# LumaFix64v1_2_sp.net
KiCad netlist of a schematic drawn in EAGLE
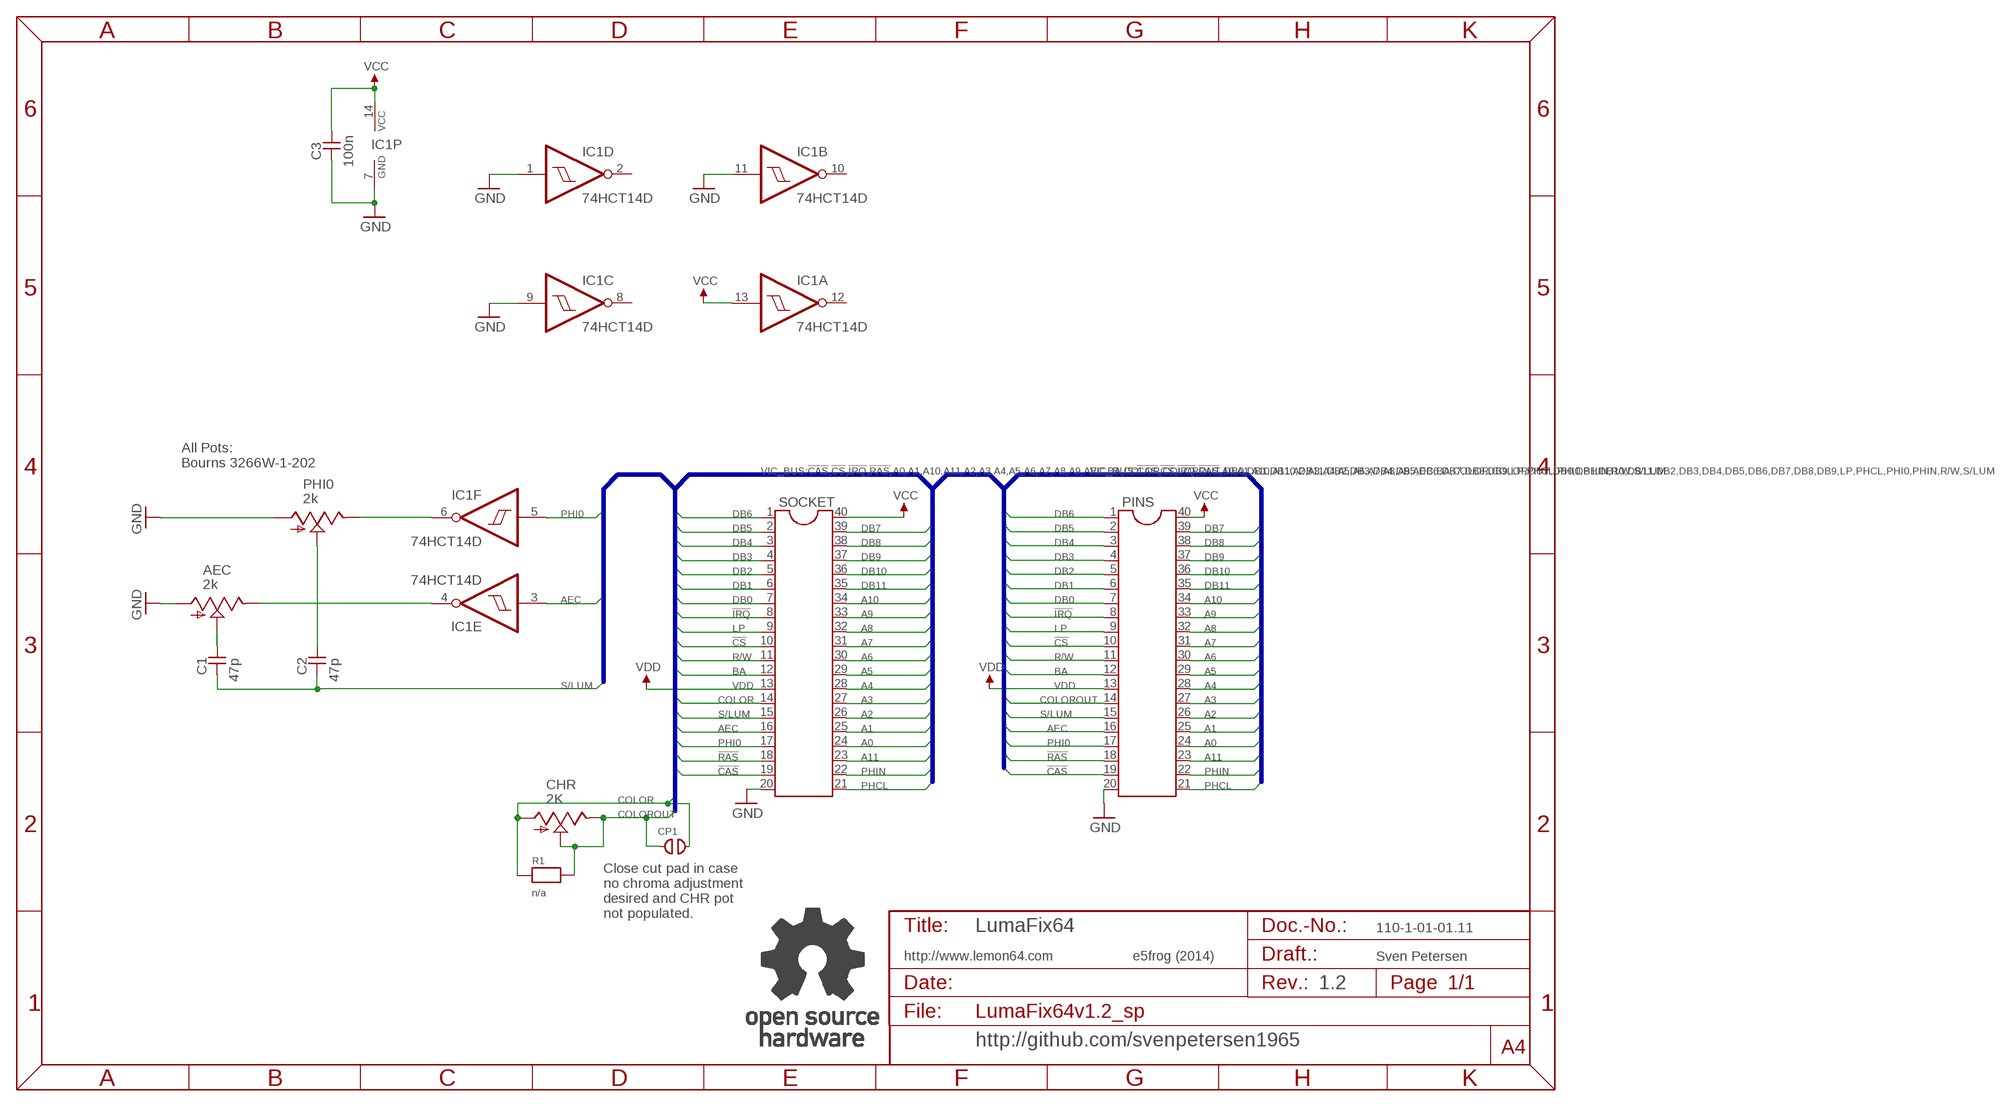
[diagram p0: schematic, sheet 1]

(export (version "E")
  (design (tool "Eeschema 10.0.6"))
  (components
    (comp (ref "AEC")
      (value "2k")
      (footprint "eagle-import:POT_B64W")
      (libsource (lib "eagle-import") (part "POT_TRIM_US-B64W"))
    )
    (comp (ref "C1")
      (value "47p")
      (footprint "eagle-import:0805")
      (libsource (lib "eagle-import") (part "C-0805"))
    )
    (comp (ref "C2")
      (value "47p")
      (footprint "eagle-import:0805")
      (libsource (lib "eagle-import") (part "C-0805"))
    )
    (comp (ref "C3")
      (value "100n")
      (footprint "eagle-import:0805")
      (libsource (lib "eagle-import") (part "C-0805"))
    )
    (comp (ref "CHR")
      (value "2K")
      (footprint "eagle-import:POT_B64W")
      (libsource (lib "eagle-import") (part "POT_TRIM_US-B64W"))
    )
    (comp (ref "CP1")
      (value "OPEN")
      (footprint "eagle-import:CP_OP")
      (libsource (lib "eagle-import") (part "OPEN"))
    )
    (comp (ref "IC1")
      (value "74HCT14D")
      (footprint "eagle-import:SO14")
      (libsource (lib "eagle-import") (part "7414DHCT"))
    )
    (comp (ref "PHI0")
      (value "2k")
      (footprint "eagle-import:POT_B64W")
      (libsource (lib "eagle-import") (part "POT_TRIM_US-B64W"))
    )
    (comp (ref "PINS")
      (value "IC-PACKAGE_DIL40_10120540")
      (footprint "eagle-import:BLK_10120540_2X20")
      (libsource (lib "eagle-import") (part "IC-PACKAGE_DIL40_10120540"))
    )
    (comp (ref "R1")
      (value "n/a")
      (footprint "eagle-import:0805")
      (libsource (lib "eagle-import") (part "R-0805"))
    )
    (comp (ref "SOCKET")
      (value "IC-PACKAGE_DIL40GS40P")
      (footprint "eagle-import:GS40P")
      (libsource (lib "eagle-import") (part "IC-PACKAGE_DIL40GS40P"))
    )
    (comp (ref "U$13")
      (value "OPEN_SOURCE_HW")
      (footprint "eagle-import:OPENHW")
      (libsource (lib "eagle-import") (part "OPEN_SOURCE_HW"))
    )
  )
  (nets
    (net (code "2") (name "/A0") (class "Default")
      (node (ref "PINS") (pin "24") (pinfunction "24_24") (pintype "passive"))
      (node (ref "SOCKET") (pin "24") (pinfunction "24_24") (pintype "passive"))
    )
    (net (code "3") (name "/A1") (class "Default")
      (node (ref "PINS") (pin "25") (pinfunction "25_25") (pintype "passive"))
      (node (ref "SOCKET") (pin "25") (pinfunction "25_25") (pintype "passive"))
    )
    (net (code "4") (name "/A2") (class "Default")
      (node (ref "PINS") (pin "26") (pinfunction "26_26") (pintype "passive"))
      (node (ref "SOCKET") (pin "26") (pinfunction "26_26") (pintype "passive"))
    )
    (net (code "5") (name "/A3") (class "Default")
      (node (ref "PINS") (pin "27") (pinfunction "27_27") (pintype "passive"))
      (node (ref "SOCKET") (pin "27") (pinfunction "27_27") (pintype "passive"))
    )
    (net (code "6") (name "/A4") (class "Default")
      (node (ref "PINS") (pin "28") (pinfunction "28_28") (pintype "passive"))
      (node (ref "SOCKET") (pin "28") (pinfunction "28_28") (pintype "passive"))
    )
    (net (code "7") (name "/A5") (class "Default")
      (node (ref "PINS") (pin "29") (pinfunction "29_29") (pintype "passive"))
      (node (ref "SOCKET") (pin "29") (pinfunction "29_29") (pintype "passive"))
    )
    (net (code "8") (name "/A6") (class "Default")
      (node (ref "PINS") (pin "30") (pinfunction "30_30") (pintype "passive"))
      (node (ref "SOCKET") (pin "30") (pinfunction "30_30") (pintype "passive"))
    )
    (net (code "9") (name "/A7") (class "Default")
      (node (ref "PINS") (pin "31") (pinfunction "31_31") (pintype "passive"))
      (node (ref "SOCKET") (pin "31") (pinfunction "31_31") (pintype "passive"))
    )
    (net (code "10") (name "/A8") (class "Default")
      (node (ref "PINS") (pin "32") (pinfunction "32_32") (pintype "passive"))
      (node (ref "SOCKET") (pin "32") (pinfunction "32_32") (pintype "passive"))
    )
    (net (code "11") (name "/A9") (class "Default")
      (node (ref "PINS") (pin "33") (pinfunction "33_33") (pintype "passive"))
      (node (ref "SOCKET") (pin "33") (pinfunction "33_33") (pintype "passive"))
    )
    (net (code "12") (name "/A10") (class "Default")
      (node (ref "PINS") (pin "34") (pinfunction "34_34") (pintype "passive"))
      (node (ref "SOCKET") (pin "34") (pinfunction "34_34") (pintype "passive"))
    )
    (net (code "13") (name "/A11") (class "Default")
      (node (ref "PINS") (pin "23") (pinfunction "23_23") (pintype "passive"))
      (node (ref "SOCKET") (pin "23") (pinfunction "23_23") (pintype "passive"))
    )
    (net (code "14") (name "/AEC") (class "Default")
      (node (ref "IC1") (pin "3") (pinfunction "I_3") (pintype "input"))
      (node (ref "PINS") (pin "16") (pinfunction "16_16") (pintype "passive"))
      (node (ref "SOCKET") (pin "16") (pinfunction "16_16") (pintype "passive"))
    )
    (net (code "15") (name "/BA") (class "Default")
      (node (ref "PINS") (pin "12") (pinfunction "12_12") (pintype "passive"))
      (node (ref "SOCKET") (pin "12") (pinfunction "12_12") (pintype "passive"))
    )
    (net (code "16") (name "/COLOR") (class "Default")
      (node (ref "CHR") (pin "A") (pinfunction "A_A") (pintype "passive"))
      (node (ref "CP1") (pin "2") (pinfunction "2_2") (pintype "passive"))
      (node (ref "R1") (pin "1") (pinfunction "1_1") (pintype "passive"))
      (node (ref "SOCKET") (pin "14") (pinfunction "14_14") (pintype "passive"))
    )
    (net (code "17") (name "/COLOROUT") (class "Default")
      (node (ref "CHR") (pin "E") (pinfunction "E_E") (pintype "passive"))
      (node (ref "CHR") (pin "S") (pinfunction "S_S") (pintype "passive"))
      (node (ref "CP1") (pin "1") (pinfunction "1_1") (pintype "passive"))
      (node (ref "PINS") (pin "14") (pinfunction "14_14") (pintype "passive"))
      (node (ref "R1") (pin "2") (pinfunction "2_2") (pintype "passive"))
    )
    (net (code "18") (name "/DB0") (class "Default")
      (node (ref "PINS") (pin "7") (pinfunction "7_7") (pintype "passive"))
      (node (ref "SOCKET") (pin "7") (pinfunction "7_7") (pintype "passive"))
    )
    (net (code "19") (name "/DB1") (class "Default")
      (node (ref "PINS") (pin "6") (pinfunction "6_6") (pintype "passive"))
      (node (ref "SOCKET") (pin "6") (pinfunction "6_6") (pintype "passive"))
    )
    (net (code "20") (name "/DB2") (class "Default")
      (node (ref "PINS") (pin "5") (pinfunction "5_5") (pintype "passive"))
      (node (ref "SOCKET") (pin "5") (pinfunction "5_5") (pintype "passive"))
    )
    (net (code "21") (name "/DB3") (class "Default")
      (node (ref "PINS") (pin "4") (pinfunction "4_4") (pintype "passive"))
      (node (ref "SOCKET") (pin "4") (pinfunction "4_4") (pintype "passive"))
    )
    (net (code "22") (name "/DB4") (class "Default")
      (node (ref "PINS") (pin "3") (pinfunction "3_3") (pintype "passive"))
      (node (ref "SOCKET") (pin "3") (pinfunction "3_3") (pintype "passive"))
    )
    (net (code "23") (name "/DB5") (class "Default")
      (node (ref "PINS") (pin "2") (pinfunction "2_2") (pintype "passive"))
      (node (ref "SOCKET") (pin "2") (pinfunction "2_2") (pintype "passive"))
    )
    (net (code "24") (name "/DB6") (class "Default")
      (node (ref "PINS") (pin "1") (pinfunction "1_1") (pintype "passive"))
      (node (ref "SOCKET") (pin "1") (pinfunction "1_1") (pintype "passive"))
    )
    (net (code "25") (name "/DB7") (class "Default")
      (node (ref "PINS") (pin "39") (pinfunction "39_39") (pintype "passive"))
      (node (ref "SOCKET") (pin "39") (pinfunction "39_39") (pintype "passive"))
    )
    (net (code "26") (name "/DB8") (class "Default")
      (node (ref "PINS") (pin "38") (pinfunction "38_38") (pintype "passive"))
      (node (ref "SOCKET") (pin "38") (pinfunction "38_38") (pintype "passive"))
    )
    (net (code "27") (name "/DB9") (class "Default")
      (node (ref "PINS") (pin "37") (pinfunction "37_37") (pintype "passive"))
      (node (ref "SOCKET") (pin "37") (pinfunction "37_37") (pintype "passive"))
    )
    (net (code "28") (name "/DB10") (class "Default")
      (node (ref "PINS") (pin "36") (pinfunction "36_36") (pintype "passive"))
      (node (ref "SOCKET") (pin "36") (pinfunction "36_36") (pintype "passive"))
    )
    (net (code "29") (name "/DB11") (class "Default")
      (node (ref "PINS") (pin "35") (pinfunction "35_35") (pintype "passive"))
      (node (ref "SOCKET") (pin "35") (pinfunction "35_35") (pintype "passive"))
    )
    (net (code "30") (name "/LP") (class "Default")
      (node (ref "PINS") (pin "9") (pinfunction "9_9") (pintype "passive"))
      (node (ref "SOCKET") (pin "9") (pinfunction "9_9") (pintype "passive"))
    )
    (net (code "31") (name "/PHCL") (class "Default")
      (node (ref "PINS") (pin "21") (pinfunction "21_21") (pintype "passive"))
      (node (ref "SOCKET") (pin "21") (pinfunction "21_21") (pintype "passive"))
    )
    (net (code "32") (name "/PHI0") (class "Default")
      (node (ref "IC1") (pin "5") (pinfunction "I_5") (pintype "input"))
      (node (ref "PINS") (pin "17") (pinfunction "17_17") (pintype "passive"))
      (node (ref "SOCKET") (pin "17") (pinfunction "17_17") (pintype "passive"))
    )
    (net (code "33") (name "/PHIN") (class "Default")
      (node (ref "PINS") (pin "22") (pinfunction "22_22") (pintype "passive"))
      (node (ref "SOCKET") (pin "22") (pinfunction "22_22") (pintype "passive"))
    )
    (net (code "34") (name "/R{slash}W") (class "Default")
      (node (ref "PINS") (pin "11") (pinfunction "11_11") (pintype "passive"))
      (node (ref "SOCKET") (pin "11") (pinfunction "11_11") (pintype "passive"))
    )
    (net (code "35") (name "/VIC_BUS:~{CAS}") (class "Default")
      (node (ref "C1") (pin "1") (pinfunction "1_1") (pintype "passive"))
      (node (ref "C2") (pin "1") (pinfunction "1_1") (pintype "passive"))
      (node (ref "PINS") (pin "15") (pinfunction "15_15") (pintype "passive"))
      (node (ref "SOCKET") (pin "15") (pinfunction "15_15") (pintype "passive"))
    )
    (net (code "37") (name "/~{CAS}") (class "Default")
      (node (ref "PINS") (pin "19") (pinfunction "19_19") (pintype "passive"))
      (node (ref "SOCKET") (pin "19") (pinfunction "19_19") (pintype "passive"))
    )
    (net (code "38") (name "/~{CS}") (class "Default")
      (node (ref "PINS") (pin "10") (pinfunction "10_10") (pintype "passive"))
      (node (ref "SOCKET") (pin "10") (pinfunction "10_10") (pintype "passive"))
    )
    (net (code "39") (name "/~{IRQ}") (class "Default")
      (node (ref "PINS") (pin "8") (pinfunction "8_8") (pintype "passive"))
      (node (ref "SOCKET") (pin "8") (pinfunction "8_8") (pintype "passive"))
    )
    (net (code "40") (name "/~{RAS}") (class "Default")
      (node (ref "PINS") (pin "18") (pinfunction "18_18") (pintype "passive"))
      (node (ref "SOCKET") (pin "18") (pinfunction "18_18") (pintype "passive"))
    )
    (net (code "41") (name "GND") (class "Default")
      (node (ref "AEC") (pin "A") (pinfunction "A_A") (pintype "passive"))
      (node (ref "C3") (pin "1") (pinfunction "1_1") (pintype "passive"))
      (node (ref "IC1") (pin "1") (pinfunction "I_1") (pintype "input"))
      (node (ref "IC1") (pin "11") (pinfunction "I_11") (pintype "input"))
      (node (ref "IC1") (pin "7") (pinfunction "GND_7") (pintype "power_in"))
      (node (ref "IC1") (pin "9") (pinfunction "I_9") (pintype "input"))
      (node (ref "PHI0") (pin "A") (pinfunction "A_A") (pintype "passive"))
      (node (ref "PINS") (pin "20") (pinfunction "20_20") (pintype "passive"))
      (node (ref "SOCKET") (pin "20") (pinfunction "20_20") (pintype "passive"))
    )
    (net (code "42") (name "Net-(AEC-PadS)") (class "Default")
      (node (ref "AEC") (pin "S") (pinfunction "S_S") (pintype "passive"))
      (node (ref "C1") (pin "2") (pinfunction "2_2") (pintype "passive"))
    )
    (net (code "43") (name "Net-(C2-Pad2)") (class "Default")
      (node (ref "C2") (pin "2") (pinfunction "2_2") (pintype "passive"))
      (node (ref "PHI0") (pin "S") (pinfunction "S_S") (pintype "passive"))
    )
    (net (code "44") (name "Net-(IC1E-O)") (class "Default")
      (node (ref "AEC") (pin "E") (pinfunction "E_E") (pintype "passive"))
      (node (ref "IC1") (pin "4") (pinfunction "O_4") (pintype "output"))
    )
    (net (code "45") (name "Net-(IC1F-O)") (class "Default")
      (node (ref "IC1") (pin "6") (pinfunction "O_6") (pintype "output"))
      (node (ref "PHI0") (pin "E") (pinfunction "E_E") (pintype "passive"))
    )
    (net (code "46") (name "VCC") (class "Default")
      (node (ref "C3") (pin "2") (pinfunction "2_2") (pintype "passive"))
      (node (ref "IC1") (pin "13") (pinfunction "I_13") (pintype "input"))
      (node (ref "IC1") (pin "14") (pinfunction "VCC_14") (pintype "power_in"))
      (node (ref "PINS") (pin "40") (pinfunction "40_40") (pintype "passive"))
      (node (ref "SOCKET") (pin "40") (pinfunction "40_40") (pintype "passive"))
    )
    (net (code "47") (name "VDD") (class "Default")
      (node (ref "PINS") (pin "13") (pinfunction "13_13") (pintype "passive"))
      (node (ref "SOCKET") (pin "13") (pinfunction "13_13") (pintype "passive"))
    )
    (net (code "48") (name "unconnected-(IC1A-O-Pad12)") (class "Default")
      (node (ref "IC1") (pin "12") (pinfunction "O_12") (pintype "output"))
    )
    (net (code "49") (name "unconnected-(IC1B-O-Pad10)") (class "Default")
      (node (ref "IC1") (pin "10") (pinfunction "O_10") (pintype "output"))
    )
    (net (code "50") (name "unconnected-(IC1C-O-Pad8)") (class "Default")
      (node (ref "IC1") (pin "8") (pinfunction "O_8") (pintype "output"))
    )
    (net (code "51") (name "unconnected-(IC1D-O-Pad2)") (class "Default")
      (node (ref "IC1") (pin "2") (pinfunction "O_2") (pintype "output"))
    )
  )
)
